# Power_VREF_P1V25.net
KiCad netlist of a schematic drawn in Altium Designer
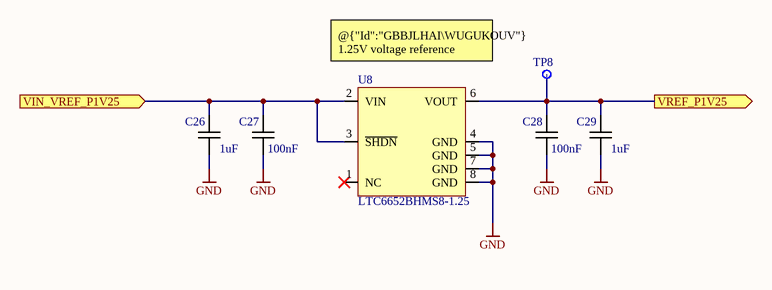
[diagram p0: Power_VREF_P1V25.SchDoc]

(export (version "E")
  (design (tool "Eeschema 10.0.6"))
  (components
    (comp (ref "C26")
      (value "1uF")
      (footprint "CAPC0603X90N")
      (description "Non-polarised capacitor")
      (fields (field (name "MANUFACTURER PART NUMBER") "CL10B105KO8NNNC"))
      (libsource (lib "Capacitors") (part "Capacitor - non polarized"))
    )
    (comp (ref "C27")
      (value "100nF")
      (footprint "CAPC0603X90N")
      (description "Non-polarised capacitor")
      (fields (field (name "MANUFACTURER PART NUMBER") "VJ0603Y104KXJCW1BC"))
      (libsource (lib "Capacitors") (part "Capacitor - non polarized"))
    )
    (comp (ref "C28")
      (value "100nF")
      (footprint "CAPC0603X90N")
      (description "Non-polarised capacitor")
      (fields (field (name "MANUFACTURER PART NUMBER") "VJ0603Y104KXJCW1BC"))
      (libsource (lib "Capacitors") (part "Capacitor - non polarized"))
    )
    (comp (ref "C29")
      (value "1uF")
      (footprint "CAPC0603X90N")
      (description "Non-polarised capacitor")
      (fields (field (name "MANUFACTURER PART NUMBER") "CL10B105KO8NNNC"))
      (libsource (lib "Capacitors") (part "Capacitor - non polarized"))
    )
    (comp (ref "TP8")
      (value "TestPoint")
      (footprint "TESTPOINT_SMD_C1P27MM")
      (description "1.27mm diameter SMD Test Point Area")
      (libsource (lib "Mechanical_and_PCB_Features") (part "Test Point"))
    )
    (comp (ref "U8")
      (value "LTC6652BHMS8-1.25")
      (footprint "MSOP65P490X110-8N")
      (description "Precision Low Drift Low Noise Buffered Reference")
      (fields (field (name "MANUFACTURER PART NUMBER") "LTC6652BHMS8-1.25#PBF"))
      (libsource (lib "ICs_and_Semiconductors") (part "LTC6652BHMS8-1.25"))
    )
  )
  (nets
    (net (code "1") (name "/VIN_VREF_P1V25") (class "Default")
      (node (ref "C26") (pin "1") (pinfunction "1_1") (pintype "passive"))
      (node (ref "C27") (pin "1") (pinfunction "1_1") (pintype "passive"))
      (node (ref "U8") (pin "2") (pinfunction "VIN_2") (pintype "passive"))
      (node (ref "U8") (pin "3") (pinfunction "~{SHDN}_3") (pintype "passive"))
    )
    (net (code "2") (name "/VREF_P1V25") (class "Default")
      (node (ref "C28") (pin "1") (pinfunction "1_1") (pintype "passive"))
      (node (ref "C29") (pin "1") (pinfunction "1_1") (pintype "passive"))
      (node (ref "TP8") (pin "1") (pinfunction "1_1") (pintype "passive"))
      (node (ref "U8") (pin "6") (pinfunction "VOUT_6") (pintype "passive"))
    )
    (net (code "3") (name "GND") (class "Default")
      (node (ref "C26") (pin "2") (pinfunction "2_2") (pintype "passive"))
      (node (ref "C27") (pin "2") (pinfunction "2_2") (pintype "passive"))
      (node (ref "C28") (pin "2") (pinfunction "2_2") (pintype "passive"))
      (node (ref "C29") (pin "2") (pinfunction "2_2") (pintype "passive"))
      (node (ref "U8") (pin "4") (pinfunction "GND_4") (pintype "power_in"))
      (node (ref "U8") (pin "5") (pinfunction "GND_5") (pintype "power_in"))
      (node (ref "U8") (pin "7") (pinfunction "GND_7") (pintype "power_in"))
      (node (ref "U8") (pin "8") (pinfunction "GND_8") (pintype "power_in"))
    )
    (net (code "4") (name "unconnected-(U8-NC-Pad1)") (class "Default")
      (node (ref "U8") (pin "1") (pinfunction "NC_1") (pintype "passive+no_connect"))
    )
  )
)
